# 31_Controlador_USB.net
KiCad netlist of a schematic drawn in Altium Designer
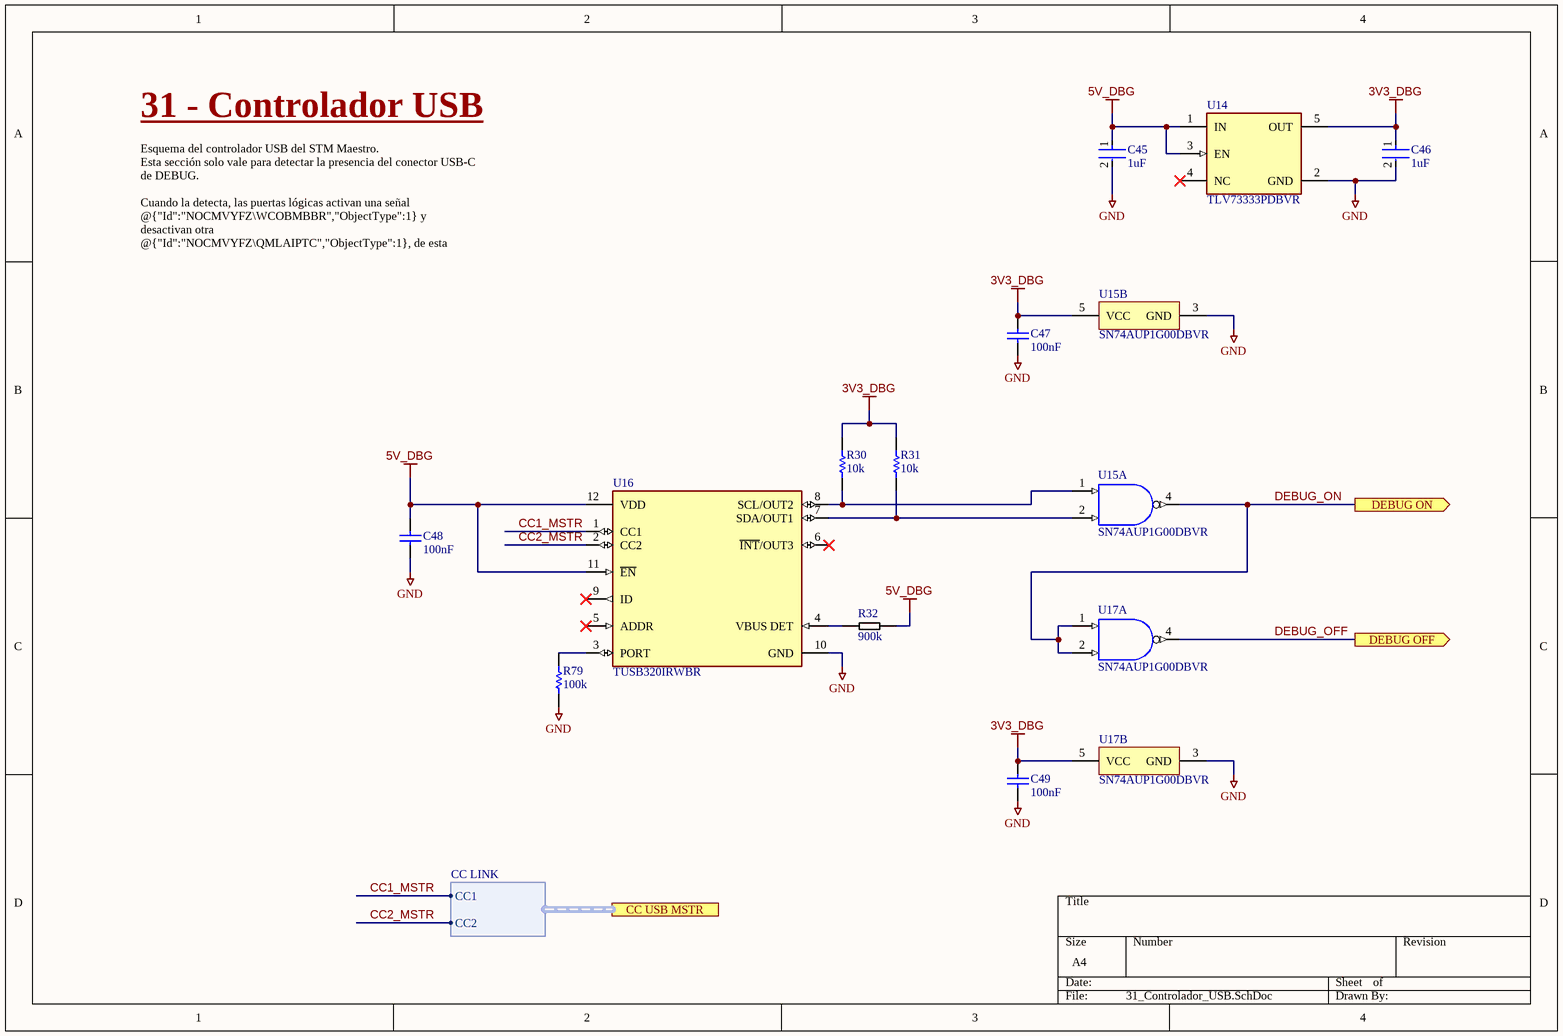
[diagram p0: 31_Controlador_USB.SchDoc]

(export (version "E")
  (design (tool "Eeschema 10.0.6"))
  (components
    (comp (ref "C45")
      (value "1uF")
      (footprint "FP-C0402C-BB-IPC_B")
      (description "CAP CER 1UF 16V X5R 0402")
      (fields (field (name "TOLERANCE") "10%"))
      (libsource (lib "Altium Content Vault") (part "b4654b650e69147ec39a6b967a45e02"))
    )
    (comp (ref "C46")
      (value "1uF")
      (footprint "FP-C0402C-BB-IPC_B")
      (description "CAP CER 1UF 16V X5R 0402")
      (fields (field (name "TOLERANCE") "10%"))
      (libsource (lib "Altium Content Vault") (part "b4654b650e69147ec39a6b967a45e02"))
    )
    (comp (ref "C47")
      (value "100nF")
      (footprint "CAPC1005X55X25NL05T05")
      (fields (field (name "MANUFACTURER") "Vitramon") (field (name "PART NUMBER") "VJ0402Y104KXJCW1BC"))
      (libsource (lib "Altium Content Vault") (part "CAP"))
    )
    (comp (ref "C48")
      (value "100nF")
      (footprint "CAPC1005X55X25NL05T05")
      (fields (field (name "MANUFACTURER") "Vitramon") (field (name "PART NUMBER") "VJ0402Y104KXJCW1BC"))
      (libsource (lib "Altium Content Vault") (part "CAP"))
    )
    (comp (ref "C49")
      (value "100nF")
      (footprint "CAPC1005X55X25NL05T05")
      (fields (field (name "MANUFACTURER") "Vitramon") (field (name "PART NUMBER") "VJ0402Y104KXJCW1BC"))
      (libsource (lib "Altium Content Vault") (part "CAP"))
    )
    (comp (ref "R30")
      (value "10k")
      (footprint "RESC1005X40X25NL05T05")
      (fields (field (name "MANUFACTURER") "Panasonic") (field (name "PART NUMBER") "ERJ-2RHD1002X"))
      (libsource (lib "Altium Content Vault") (part "RES"))
    )
    (comp (ref "R31")
      (value "10k")
      (footprint "RESC1005X40X25NL05T05")
      (fields (field (name "MANUFACTURER") "Panasonic") (field (name "PART NUMBER") "ERJ-2RHD1002X"))
      (libsource (lib "Altium Content Vault") (part "RES"))
    )
    (comp (ref "R32")
      (value "900k")
      (footprint "RES 1206")
      (description "900k Resistor 200V 1206 0.5%")
      (libsource (lib "Esquemas") (part "RT1206CRE07900KL"))
    )
    (comp (ref "R79")
      (value "100k")
      (footprint "RESC1005X40X25ML10T10")
      (fields (field (name "PART NUMBER") "SG73P1ETTP1003F") (field (name "MANUFACTURER") "KOA Speer"))
      (libsource (lib "Altium Content Vault") (part "RES"))
    )
    (comp (ref "U14")
      (value "TLV73333PDBVR")
      (footprint "FP-DBV0005A-MFG")
      (description "IC REG LINEAR 3.3V 300MA SOT23-5")
      (fields
        (field (name "MANUFACTURER") "Texas Instruments")
        (field (name "OCTOPART") "https://octopart.com/tlv73333pdbvr-texas+instruments-51080890")
      )
      (libsource (lib "Altium Content Vault") (part "10cdd6a861ce8db355dac0efc8b397e"))
    )
    (comp (ref "U15")
      (value "SN74AUP1G00DBVR")
      (footprint "DBV0005A_N")
      (description "Low-Power Single Two-Input Positive-NAND Gate, DBV0005A, LARGE T&R")
      (fields
        (field (name "GENERIC PART NUMBER") "SN74AUP1G00")
        (field (name "MANUFACTURER") "Texas Instruments")
      )
      (libsource (lib "Altium Content Vault") (part "TI-SN74XXX1XXXX-5"))
    )
    (comp (ref "U16")
      (value "TUSB320IRWBR")
      (footprint "FP-RWB0012A-MFG")
      (description "IC INTERFACE SPECIALIZED 12X2QFN")
      (libsource (lib "Altium Content Vault") (part "76af6d7f95a64df20dc6dc148ef600c"))
    )
    (comp (ref "U17")
      (value "SN74AUP1G00DBVR")
      (footprint "DBV0005A_N")
      (description "Low-Power Single Two-Input Positive-NAND Gate, DBV0005A, LARGE T&R")
      (fields
        (field (name "GENERIC PART NUMBER") "SN74AUP1G00")
        (field (name "MANUFACTURER") "Texas Instruments")
      )
      (libsource (lib "Altium Content Vault") (part "TI-SN74XXX1XXXX-5"))
    )
  )
  (nets
    (net (code "3") (name "/CC1_MSTR") (class "Default")
      (node (ref "U16") (pin "1") (pinfunction "CC1_1") (pintype "bidirectional"))
    )
    (net (code "4") (name "/CC2_MSTR") (class "Default")
      (node (ref "U16") (pin "2") (pinfunction "CC2_2") (pintype "bidirectional"))
    )
    (net (code "5") (name "/DEBUG_OFF") (class "Default")
      (node (ref "U17") (pin "4") (pinfunction "Y_4") (pintype "output"))
    )
    (net (code "6") (name "/DEBUG_ON") (class "Default")
      (node (ref "U15") (pin "4") (pinfunction "Y_4") (pintype "output"))
      (node (ref "U17") (pin "1") (pinfunction "A_1") (pintype "input"))
      (node (ref "U17") (pin "2") (pinfunction "B_2") (pintype "input"))
    )
    (net (code "8") (name "3V3_DBG") (class "Default")
      (node (ref "C46") (pin "1") (pinfunction "1_1") (pintype "passive"))
      (node (ref "C47") (pin "2") (pinfunction "2_2") (pintype "passive"))
      (node (ref "C49") (pin "2") (pinfunction "2_2") (pintype "passive"))
      (node (ref "R30") (pin "2") (pinfunction "2_2") (pintype "passive"))
      (node (ref "R31") (pin "2") (pinfunction "2_2") (pintype "passive"))
      (node (ref "U14") (pin "5") (pinfunction "OUT_5") (pintype "power_in"))
      (node (ref "U15") (pin "5") (pinfunction "VCC_5") (pintype "power_in"))
      (node (ref "U17") (pin "5") (pinfunction "VCC_5") (pintype "power_in"))
    )
    (net (code "9") (name "5V_DBG") (class "Default")
      (node (ref "C45") (pin "1") (pinfunction "1_1") (pintype "passive"))
      (node (ref "C48") (pin "2") (pinfunction "2_2") (pintype "passive"))
      (node (ref "R32") (pin "1") (pintype "passive"))
      (node (ref "U14") (pin "1") (pinfunction "IN_1") (pintype "passive"))
      (node (ref "U14") (pin "3") (pinfunction "EN_3") (pintype "input"))
      (node (ref "U16") (pin "11") (pinfunction "~{EN}_11") (pintype "input"))
      (node (ref "U16") (pin "12") (pinfunction "VDD_12") (pintype "passive"))
    )
    (net (code "10") (name "GND") (class "Default")
      (node (ref "C45") (pin "2") (pinfunction "2_2") (pintype "passive"))
      (node (ref "C46") (pin "2") (pinfunction "2_2") (pintype "passive"))
      (node (ref "C47") (pin "1") (pinfunction "1_1") (pintype "passive"))
      (node (ref "C48") (pin "1") (pinfunction "1_1") (pintype "passive"))
      (node (ref "C49") (pin "1") (pinfunction "1_1") (pintype "passive"))
      (node (ref "R79") (pin "1") (pinfunction "1_1") (pintype "passive"))
      (node (ref "U14") (pin "2") (pinfunction "GND_2") (pintype "passive"))
      (node (ref "U15") (pin "3") (pinfunction "GND_3") (pintype "power_in"))
      (node (ref "U16") (pin "10") (pinfunction "GND_10") (pintype "passive"))
      (node (ref "U17") (pin "3") (pinfunction "GND_3") (pintype "power_in"))
    )
    (net (code "11") (name "Net-(U15A-A)") (class "Default")
      (node (ref "R30") (pin "1") (pinfunction "1_1") (pintype "passive"))
      (node (ref "U15") (pin "1") (pinfunction "A_1") (pintype "input"))
      (node (ref "U16") (pin "8") (pinfunction "SCL/OUT2_8") (pintype "bidirectional"))
    )
    (net (code "12") (name "Net-(U15A-B)") (class "Default")
      (node (ref "R31") (pin "1") (pinfunction "1_1") (pintype "passive"))
      (node (ref "U15") (pin "2") (pinfunction "B_2") (pintype "input"))
      (node (ref "U16") (pin "7") (pinfunction "SDA/OUT1_7") (pintype "bidirectional"))
    )
    (net (code "13") (name "Net-(U16-PORT)") (class "Default")
      (node (ref "R79") (pin "2") (pinfunction "2_2") (pintype "passive"))
      (node (ref "U16") (pin "3") (pinfunction "PORT_3") (pintype "bidirectional"))
    )
    (net (code "14") (name "Net-(U16-VBUS_DET)") (class "Default")
      (node (ref "R32") (pin "2") (pintype "passive"))
      (node (ref "U16") (pin "4") (pinfunction "VBUS_DET_4") (pintype "input"))
    )
    (net (code "15") (name "unconnected-(U14-NC-Pad4)") (class "Default")
      (node (ref "U14") (pin "4") (pinfunction "NC_4") (pintype "passive+no_connect"))
    )
    (net (code "16") (name "unconnected-(U16-ADDR-Pad5)") (class "Default")
      (node (ref "U16") (pin "5") (pinfunction "ADDR_5") (pintype "input+no_connect"))
    )
    (net (code "17") (name "unconnected-(U16-ID-Pad9)") (class "Default")
      (node (ref "U16") (pin "9") (pinfunction "ID_9") (pintype "output+no_connect"))
    )
    (net (code "18") (name "unconnected-(U16-~{INT}{slash}OUT3-Pad6)") (class "Default")
      (node (ref "U16") (pin "6") (pinfunction "~{INT}/OUT3_6") (pintype "bidirectional+no_connect"))
    )
  )
)
